# nola5a.net
KiCad netlist of a schematic drawn in EAGLE
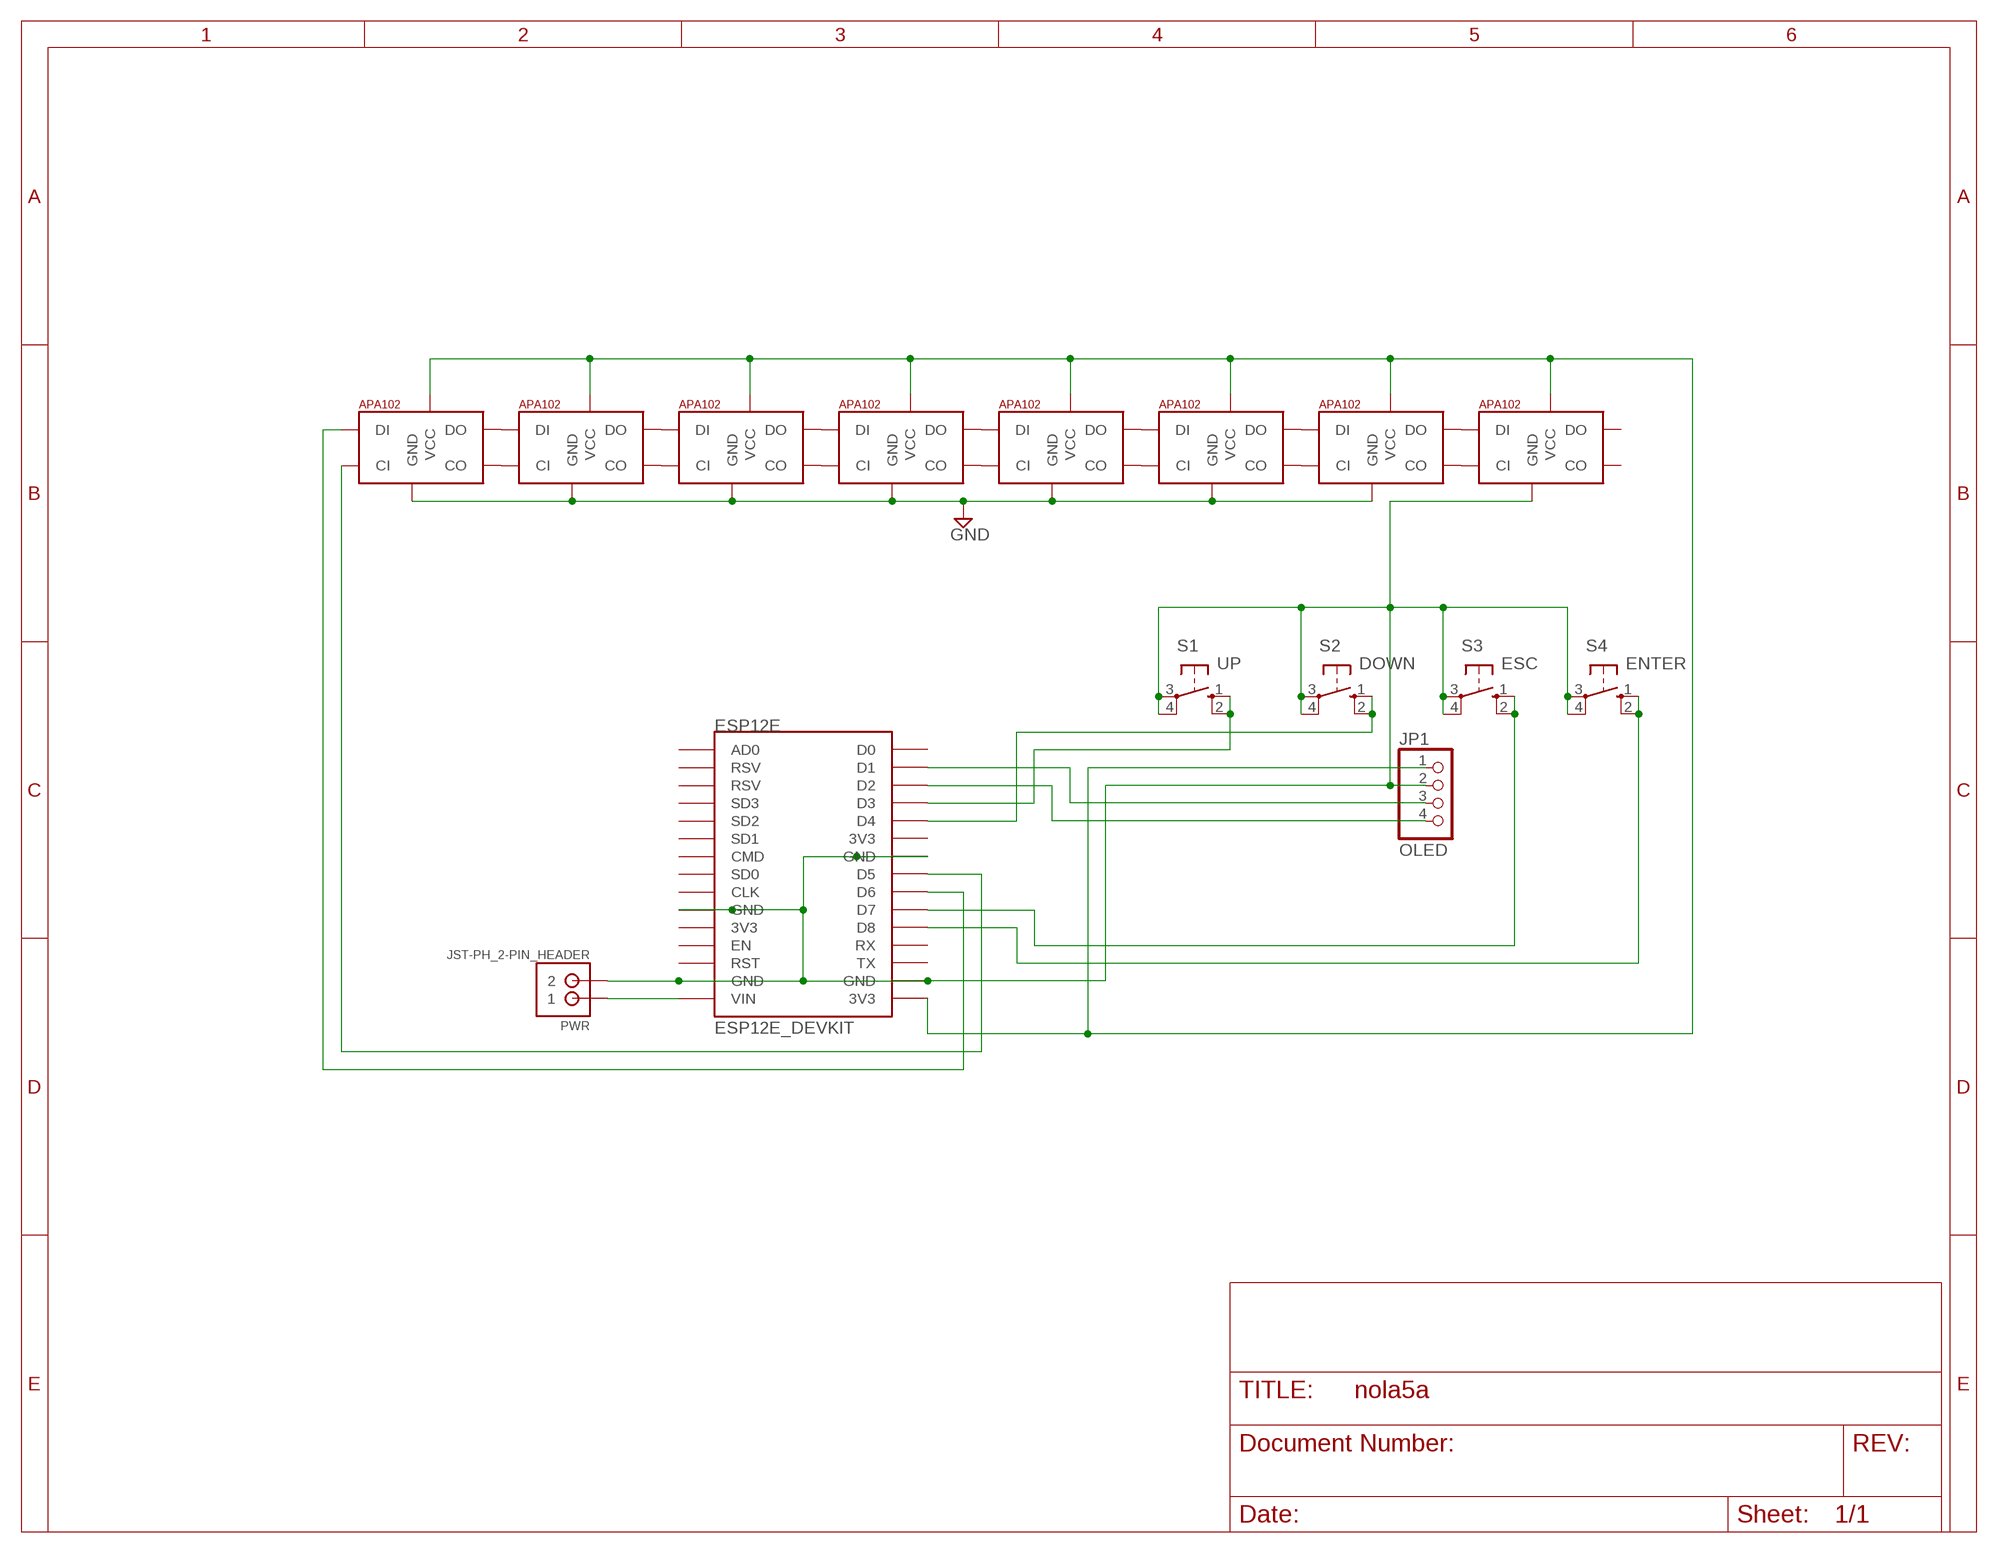
[diagram p0: schematic, sheet 1]

(export (version "E")
  (design (tool "Eeschema 10.0.6"))
  (components
    (comp (ref "ESP12E")
      (value "ESP12E_DEVKIT")
      (footprint "eagle-import:ESP12E_DEVKIT")
      (libsource (lib "eagle-import") (part "ESP12E_DEVKIT"))
    )
    (comp (ref "JP1")
      (value "OLED")
      (footprint "eagle-import:1X04")
      (libsource (lib "eagle-import") (part "PINHD-1X4"))
    )
    (comp (ref "LED1")
      (value "APA1025050")
      (footprint "eagle-import:APA102_5050")
      (libsource (lib "eagle-import") (part "APA1025050"))
    )
    (comp (ref "LED2")
      (value "APA1025050")
      (footprint "eagle-import:APA102_5050")
      (libsource (lib "eagle-import") (part "APA1025050"))
    )
    (comp (ref "LED3")
      (value "APA1025050")
      (footprint "eagle-import:APA102_5050")
      (libsource (lib "eagle-import") (part "APA1025050"))
    )
    (comp (ref "LED4")
      (value "APA1025050")
      (footprint "eagle-import:APA102_5050")
      (libsource (lib "eagle-import") (part "APA1025050"))
    )
    (comp (ref "LED5")
      (value "APA1025050")
      (footprint "eagle-import:APA102_5050")
      (libsource (lib "eagle-import") (part "APA1025050"))
    )
    (comp (ref "LED6")
      (value "APA1025050")
      (footprint "eagle-import:APA102_5050")
      (libsource (lib "eagle-import") (part "APA1025050"))
    )
    (comp (ref "LED7")
      (value "APA1025050")
      (footprint "eagle-import:APA102_5050")
      (libsource (lib "eagle-import") (part "APA1025050"))
    )
    (comp (ref "LED8")
      (value "APA1025050")
      (footprint "eagle-import:APA102_5050")
      (libsource (lib "eagle-import") (part "APA1025050"))
    )
    (comp (ref "PWR")
      (value "JST-PH_2-PIN_HEADER")
      (footprint "eagle-import:JST_B2B-PH_HEADER")
      (libsource (lib "eagle-import") (part "JST-PH_2-PIN_HEADER"))
    )
    (comp (ref "S1")
      (value "UP")
      (footprint "eagle-import:B3F-10XX")
      (fields (field (name "MPN") "B3F-1000"))
      (libsource (lib "eagle-import") (part "10-XX"))
    )
    (comp (ref "S2")
      (value "DOWN")
      (footprint "eagle-import:B3F-10XX")
      (fields (field (name "MPN") "B3F-1000"))
      (libsource (lib "eagle-import") (part "10-XX"))
    )
    (comp (ref "S3")
      (value "ESC")
      (footprint "eagle-import:B3F-10XX")
      (fields (field (name "MPN") "B3F-1000"))
      (libsource (lib "eagle-import") (part "10-XX"))
    )
    (comp (ref "S4")
      (value "ENTER")
      (footprint "eagle-import:B3F-10XX")
      (fields (field (name "MPN") "B3F-1000"))
      (libsource (lib "eagle-import") (part "10-XX"))
    )
  )
  (nets
    (net (code "1") (name "GND") (class "Default")
      (node (ref "ESP12E") (pin "GND@0") (pinfunction "GND_GND@0") (pintype "bidirectional"))
      (node (ref "ESP12E") (pin "GND@1") (pinfunction "GND_GND@1") (pintype "bidirectional"))
      (node (ref "ESP12E") (pin "GND@2") (pinfunction "GND_GND@2") (pintype "bidirectional"))
      (node (ref "ESP12E") (pin "GND@3") (pinfunction "GND_GND@3") (pintype "bidirectional"))
      (node (ref "JP1") (pin "2") (pinfunction "2_2") (pintype "passive"))
      (node (ref "LED1") (pin "6") (pinfunction "GND_6") (pintype "bidirectional"))
      (node (ref "LED2") (pin "6") (pinfunction "GND_6") (pintype "bidirectional"))
      (node (ref "LED3") (pin "6") (pinfunction "GND_6") (pintype "bidirectional"))
      (node (ref "LED4") (pin "6") (pinfunction "GND_6") (pintype "bidirectional"))
      (node (ref "LED5") (pin "6") (pinfunction "GND_6") (pintype "bidirectional"))
      (node (ref "LED6") (pin "6") (pinfunction "GND_6") (pintype "bidirectional"))
      (node (ref "LED7") (pin "6") (pinfunction "GND_6") (pintype "bidirectional"))
      (node (ref "LED8") (pin "6") (pinfunction "GND_6") (pintype "bidirectional"))
      (node (ref "PWR") (pin "P2") (pinfunction "2_P2") (pintype "bidirectional"))
      (node (ref "S1") (pin "3") (pinfunction "P_3") (pintype "passive"))
      (node (ref "S1") (pin "4") (pinfunction "P1_4") (pintype "passive"))
      (node (ref "S2") (pin "3") (pinfunction "P_3") (pintype "passive"))
      (node (ref "S2") (pin "4") (pinfunction "P1_4") (pintype "passive"))
      (node (ref "S3") (pin "3") (pinfunction "P_3") (pintype "passive"))
      (node (ref "S3") (pin "4") (pinfunction "P1_4") (pintype "passive"))
      (node (ref "S4") (pin "3") (pinfunction "P_3") (pintype "passive"))
      (node (ref "S4") (pin "4") (pinfunction "P1_4") (pintype "passive"))
    )
    (net (code "2") (name "Net-(ESP12E-PadD1)") (class "Default")
      (node (ref "ESP12E") (pin "D1") (pinfunction "D1_D1") (pintype "bidirectional"))
      (node (ref "JP1") (pin "3") (pinfunction "3_3") (pintype "passive"))
    )
    (net (code "3") (name "Net-(ESP12E-PadD2)") (class "Default")
      (node (ref "ESP12E") (pin "D2") (pinfunction "D2_D2") (pintype "bidirectional"))
      (node (ref "JP1") (pin "4") (pinfunction "4_4") (pintype "passive"))
    )
    (net (code "4") (name "Net-(LED1-CI)") (class "Default")
      (node (ref "ESP12E") (pin "D5") (pinfunction "D5_D5") (pintype "bidirectional"))
      (node (ref "LED1") (pin "5") (pinfunction "CI_5") (pintype "bidirectional"))
    )
    (net (code "5") (name "Net-(LED1-CO)") (class "Default")
      (node (ref "LED1") (pin "2") (pinfunction "CO_2") (pintype "bidirectional"))
      (node (ref "LED2") (pin "5") (pinfunction "CI_5") (pintype "bidirectional"))
    )
    (net (code "6") (name "Net-(LED1-DI)") (class "Default")
      (node (ref "ESP12E") (pin "D6") (pinfunction "D6_D6") (pintype "bidirectional"))
      (node (ref "LED1") (pin "4") (pinfunction "DI_4") (pintype "bidirectional"))
    )
    (net (code "7") (name "Net-(LED1-DO)") (class "Default")
      (node (ref "LED1") (pin "3") (pinfunction "DO_3") (pintype "bidirectional"))
      (node (ref "LED2") (pin "4") (pinfunction "DI_4") (pintype "bidirectional"))
    )
    (net (code "8") (name "Net-(LED1-VCC)") (class "Default")
      (node (ref "ESP12E") (pin "3V3@2") (pinfunction "3V3_3V3@2") (pintype "bidirectional"))
      (node (ref "JP1") (pin "1") (pinfunction "1_1") (pintype "passive"))
      (node (ref "LED1") (pin "1") (pinfunction "VCC_1") (pintype "bidirectional"))
      (node (ref "LED2") (pin "1") (pinfunction "VCC_1") (pintype "bidirectional"))
      (node (ref "LED3") (pin "1") (pinfunction "VCC_1") (pintype "bidirectional"))
      (node (ref "LED4") (pin "1") (pinfunction "VCC_1") (pintype "bidirectional"))
      (node (ref "LED5") (pin "1") (pinfunction "VCC_1") (pintype "bidirectional"))
      (node (ref "LED6") (pin "1") (pinfunction "VCC_1") (pintype "bidirectional"))
      (node (ref "LED7") (pin "1") (pinfunction "VCC_1") (pintype "bidirectional"))
      (node (ref "LED8") (pin "1") (pinfunction "VCC_1") (pintype "bidirectional"))
    )
    (net (code "9") (name "Net-(LED2-CO)") (class "Default")
      (node (ref "LED2") (pin "2") (pinfunction "CO_2") (pintype "bidirectional"))
      (node (ref "LED3") (pin "5") (pinfunction "CI_5") (pintype "bidirectional"))
    )
    (net (code "10") (name "Net-(LED2-DO)") (class "Default")
      (node (ref "LED2") (pin "3") (pinfunction "DO_3") (pintype "bidirectional"))
      (node (ref "LED3") (pin "4") (pinfunction "DI_4") (pintype "bidirectional"))
    )
    (net (code "11") (name "Net-(LED3-CO)") (class "Default")
      (node (ref "LED3") (pin "2") (pinfunction "CO_2") (pintype "bidirectional"))
      (node (ref "LED4") (pin "5") (pinfunction "CI_5") (pintype "bidirectional"))
    )
    (net (code "12") (name "Net-(LED3-DO)") (class "Default")
      (node (ref "LED3") (pin "3") (pinfunction "DO_3") (pintype "bidirectional"))
      (node (ref "LED4") (pin "4") (pinfunction "DI_4") (pintype "bidirectional"))
    )
    (net (code "13") (name "Net-(LED4-CO)") (class "Default")
      (node (ref "LED4") (pin "2") (pinfunction "CO_2") (pintype "bidirectional"))
      (node (ref "LED5") (pin "5") (pinfunction "CI_5") (pintype "bidirectional"))
    )
    (net (code "14") (name "Net-(LED4-DO)") (class "Default")
      (node (ref "LED4") (pin "3") (pinfunction "DO_3") (pintype "bidirectional"))
      (node (ref "LED5") (pin "4") (pinfunction "DI_4") (pintype "bidirectional"))
    )
    (net (code "15") (name "Net-(LED5-CO)") (class "Default")
      (node (ref "LED5") (pin "2") (pinfunction "CO_2") (pintype "bidirectional"))
      (node (ref "LED6") (pin "5") (pinfunction "CI_5") (pintype "bidirectional"))
    )
    (net (code "16") (name "Net-(LED5-DO)") (class "Default")
      (node (ref "LED5") (pin "3") (pinfunction "DO_3") (pintype "bidirectional"))
      (node (ref "LED6") (pin "4") (pinfunction "DI_4") (pintype "bidirectional"))
    )
    (net (code "17") (name "Net-(LED6-CO)") (class "Default")
      (node (ref "LED6") (pin "2") (pinfunction "CO_2") (pintype "bidirectional"))
      (node (ref "LED7") (pin "5") (pinfunction "CI_5") (pintype "bidirectional"))
    )
    (net (code "18") (name "Net-(LED6-DO)") (class "Default")
      (node (ref "LED6") (pin "3") (pinfunction "DO_3") (pintype "bidirectional"))
      (node (ref "LED7") (pin "4") (pinfunction "DI_4") (pintype "bidirectional"))
    )
    (net (code "19") (name "Net-(LED7-CO)") (class "Default")
      (node (ref "LED7") (pin "2") (pinfunction "CO_2") (pintype "bidirectional"))
      (node (ref "LED8") (pin "5") (pinfunction "CI_5") (pintype "bidirectional"))
    )
    (net (code "20") (name "Net-(LED7-DO)") (class "Default")
      (node (ref "LED7") (pin "3") (pinfunction "DO_3") (pintype "bidirectional"))
      (node (ref "LED8") (pin "4") (pinfunction "DI_4") (pintype "bidirectional"))
    )
    (net (code "21") (name "Net-(PWR-1)") (class "Default")
      (node (ref "ESP12E") (pin "VIN") (pinfunction "VIN_VIN") (pintype "bidirectional"))
      (node (ref "PWR") (pin "P1") (pinfunction "1_P1") (pintype "bidirectional"))
    )
    (net (code "22") (name "Net-(S1-S)") (class "Default")
      (node (ref "ESP12E") (pin "D3") (pinfunction "D3_D3") (pintype "bidirectional"))
      (node (ref "S1") (pin "1") (pinfunction "S_1") (pintype "passive"))
      (node (ref "S1") (pin "2") (pinfunction "S1_2") (pintype "passive"))
    )
    (net (code "23") (name "Net-(S2-S)") (class "Default")
      (node (ref "ESP12E") (pin "D4") (pinfunction "D4_D4") (pintype "bidirectional"))
      (node (ref "S2") (pin "1") (pinfunction "S_1") (pintype "passive"))
      (node (ref "S2") (pin "2") (pinfunction "S1_2") (pintype "passive"))
    )
    (net (code "24") (name "Net-(S3-S)") (class "Default")
      (node (ref "ESP12E") (pin "D7") (pinfunction "D7_D7") (pintype "bidirectional"))
      (node (ref "S3") (pin "1") (pinfunction "S_1") (pintype "passive"))
      (node (ref "S3") (pin "2") (pinfunction "S1_2") (pintype "passive"))
    )
    (net (code "25") (name "Net-(S4-S)") (class "Default")
      (node (ref "ESP12E") (pin "D8") (pinfunction "D8_D8") (pintype "bidirectional"))
      (node (ref "S4") (pin "1") (pinfunction "S_1") (pintype "passive"))
      (node (ref "S4") (pin "2") (pinfunction "S1_2") (pintype "passive"))
    )
    (net (code "26") (name "unconnected-(ESP12E-3V3-Pad3V3@0)") (class "Default")
      (node (ref "ESP12E") (pin "3V3@0") (pinfunction "3V3_3V3@0") (pintype "bidirectional"))
    )
    (net (code "27") (name "unconnected-(ESP12E-3V3-Pad3V3@1)") (class "Default")
      (node (ref "ESP12E") (pin "3V3@1") (pinfunction "3V3_3V3@1") (pintype "bidirectional"))
    )
    (net (code "28") (name "unconnected-(ESP12E-PadAD0)") (class "Default")
      (node (ref "ESP12E") (pin "AD0") (pinfunction "AD0_AD0") (pintype "bidirectional"))
    )
    (net (code "29") (name "unconnected-(ESP12E-PadCLK)") (class "Default")
      (node (ref "ESP12E") (pin "CLK") (pinfunction "CLK_CLK") (pintype "bidirectional"))
    )
    (net (code "30") (name "unconnected-(ESP12E-PadCMD)") (class "Default")
      (node (ref "ESP12E") (pin "CMD") (pinfunction "CMD_CMD") (pintype "bidirectional"))
    )
    (net (code "31") (name "unconnected-(ESP12E-PadD0)") (class "Default")
      (node (ref "ESP12E") (pin "D0") (pinfunction "D0_D0") (pintype "bidirectional"))
    )
    (net (code "32") (name "unconnected-(ESP12E-PadEN)") (class "Default")
      (node (ref "ESP12E") (pin "EN") (pinfunction "EN_EN") (pintype "bidirectional"))
    )
    (net (code "33") (name "unconnected-(ESP12E-PadRST)") (class "Default")
      (node (ref "ESP12E") (pin "RST") (pinfunction "RST_RST") (pintype "bidirectional"))
    )
    (net (code "34") (name "unconnected-(ESP12E-PadRX)") (class "Default")
      (node (ref "ESP12E") (pin "RX") (pinfunction "RX_RX") (pintype "bidirectional"))
    )
    (net (code "35") (name "unconnected-(ESP12E-PadSD0)") (class "Default")
      (node (ref "ESP12E") (pin "SD0") (pinfunction "SD0_SD0") (pintype "bidirectional"))
    )
    (net (code "36") (name "unconnected-(ESP12E-PadSD1)") (class "Default")
      (node (ref "ESP12E") (pin "SD1") (pinfunction "SD1_SD1") (pintype "bidirectional"))
    )
    (net (code "37") (name "unconnected-(ESP12E-PadSD2)") (class "Default")
      (node (ref "ESP12E") (pin "SD2") (pinfunction "SD2_SD2") (pintype "bidirectional"))
    )
    (net (code "38") (name "unconnected-(ESP12E-PadSD3)") (class "Default")
      (node (ref "ESP12E") (pin "SD3") (pinfunction "SD3_SD3") (pintype "bidirectional"))
    )
    (net (code "39") (name "unconnected-(ESP12E-PadTX)") (class "Default")
      (node (ref "ESP12E") (pin "TX") (pinfunction "TX_TX") (pintype "bidirectional"))
    )
    (net (code "40") (name "unconnected-(ESP12E-RSV-PadRSV@0)") (class "Default")
      (node (ref "ESP12E") (pin "RSV@0") (pinfunction "RSV_RSV@0") (pintype "bidirectional"))
    )
    (net (code "41") (name "unconnected-(ESP12E-RSV-PadRSV@1)") (class "Default")
      (node (ref "ESP12E") (pin "RSV@1") (pinfunction "RSV_RSV@1") (pintype "bidirectional"))
    )
    (net (code "42") (name "unconnected-(LED8-CO-Pad2)") (class "Default")
      (node (ref "LED8") (pin "2") (pinfunction "CO_2") (pintype "bidirectional"))
    )
    (net (code "43") (name "unconnected-(LED8-DO-Pad3)") (class "Default")
      (node (ref "LED8") (pin "3") (pinfunction "DO_3") (pintype "bidirectional"))
    )
  )
)
